# Cellphone_Incoming_Call_Detector.net
KiCad netlist of a schematic drawn in EAGLE
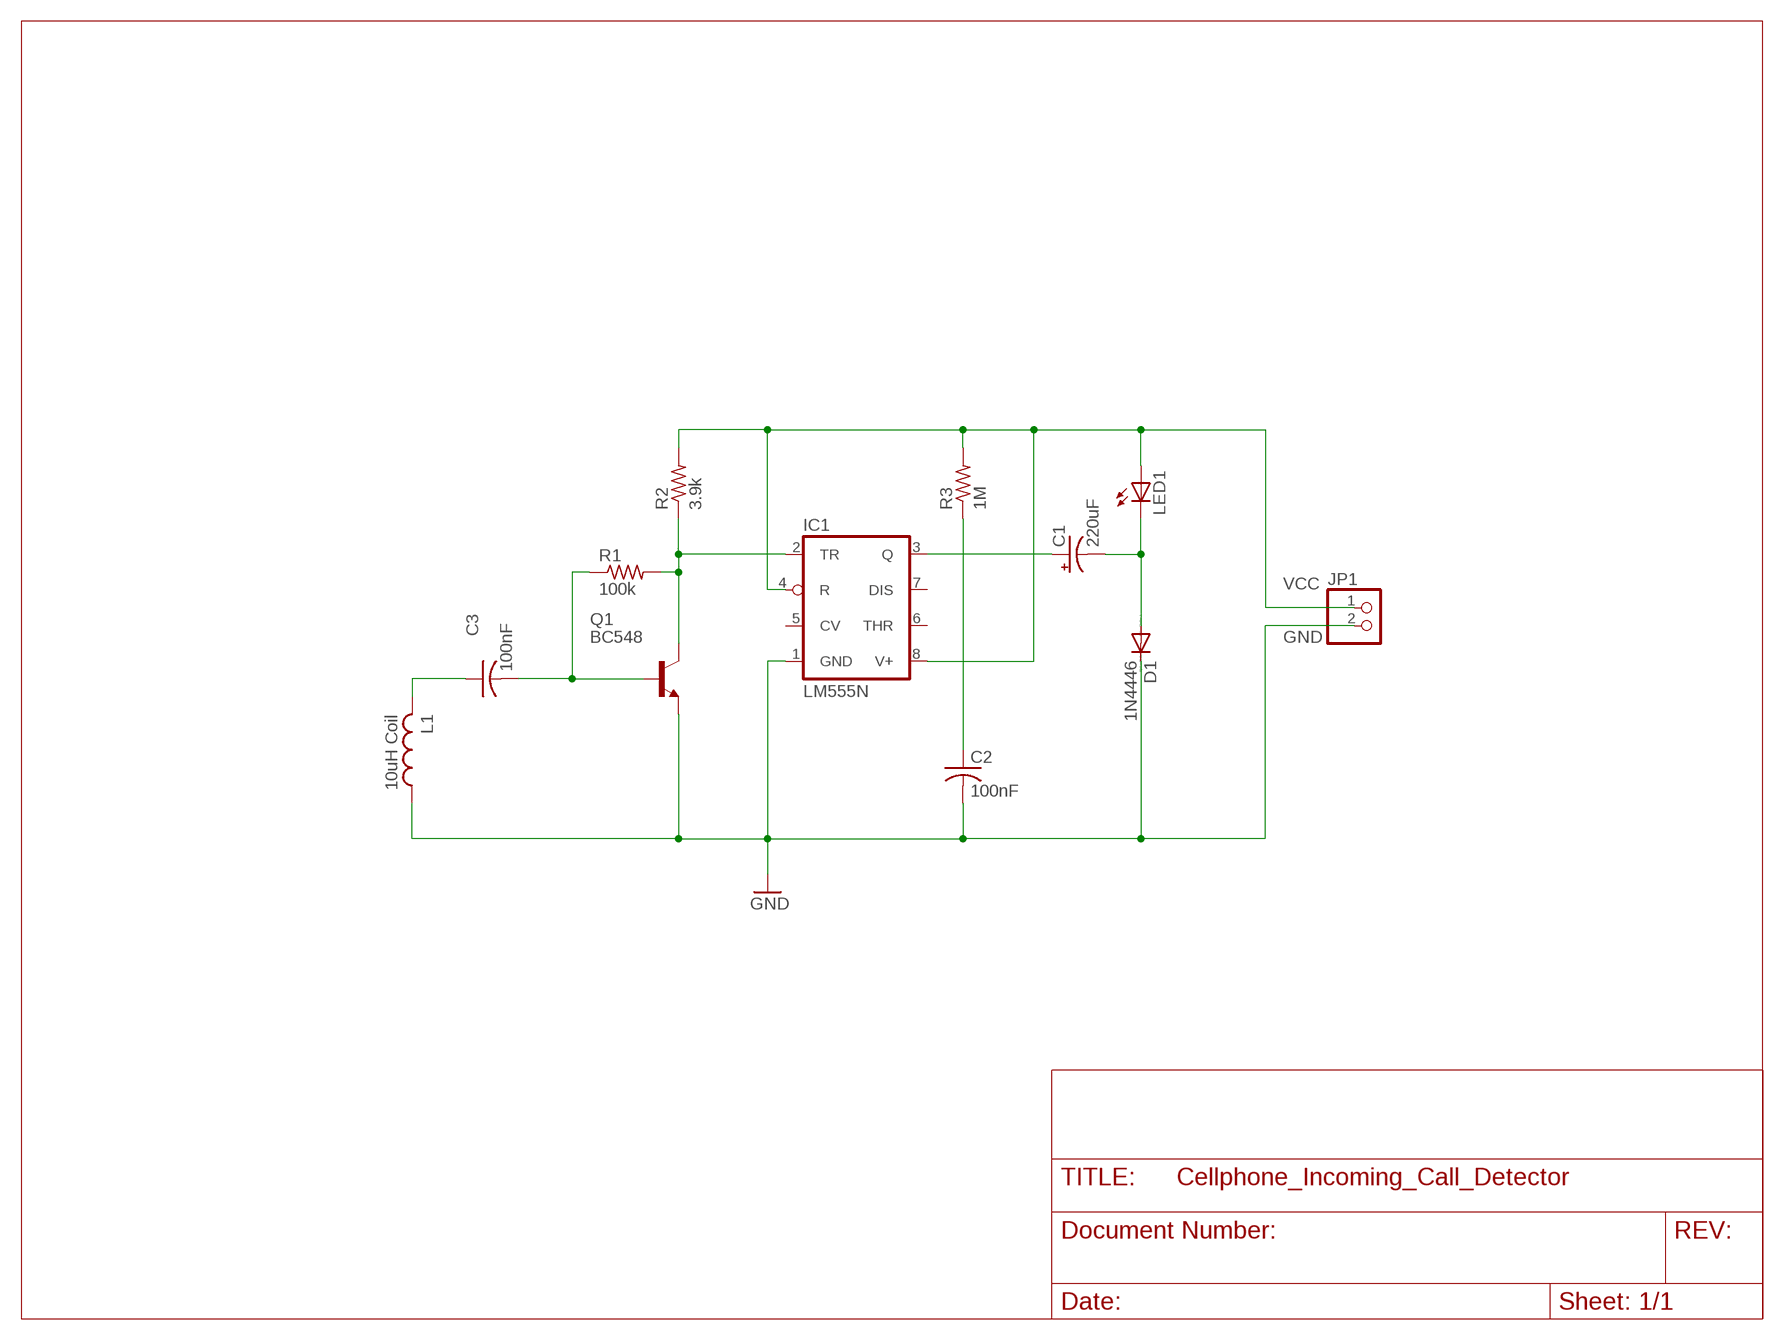
[diagram p0: schematic, sheet 1]

(export (version "E")
  (design (tool "Eeschema 10.0.6"))
  (components
    (comp (ref "C1")
      (value "220uF")
      (footprint "eagle-import:E3,5-8")
      (libsource (lib "eagle-import") (part "CPOL-USE3.5-8"))
    )
    (comp (ref "C2")
      (value "100nF")
      (footprint "eagle-import:C025-025X050")
      (libsource (lib "eagle-import") (part "C-US025-025X050"))
    )
    (comp (ref "C3")
      (value "100nF")
      (footprint "eagle-import:C025-025X050")
      (libsource (lib "eagle-import") (part "C-US025-025X050"))
    )
    (comp (ref "D1")
      (value "1N4446")
      (footprint "eagle-import:DO35-10")
      (libsource (lib "eagle-import") (part "1N4446"))
    )
    (comp (ref "IC1")
      (value "LM555N")
      (footprint "eagle-import:DIL08")
      (libsource (lib "eagle-import") (part "555NLM"))
    )
    (comp (ref "JP1")
      (value "PINHD-1X2")
      (footprint "eagle-import:1X02")
      (libsource (lib "eagle-import") (part "PINHD-1X2"))
    )
    (comp (ref "L1")
      (value "10uH Coil")
      (footprint "eagle-import:0204_7")
      (libsource (lib "eagle-import") (part "L-US0204/7"))
    )
    (comp (ref "LED1")
      (value "LED5MM")
      (footprint "eagle-import:LED5MM")
      (libsource (lib "eagle-import") (part "LED5MM"))
    )
    (comp (ref "Q1")
      (value "BC548")
      (footprint "eagle-import:TO92-EBC")
      (libsource (lib "eagle-import") (part "BC548"))
    )
    (comp (ref "R1")
      (value "100k")
      (footprint "eagle-import:0204_7")
      (libsource (lib "eagle-import") (part "R-US_0204/7"))
    )
    (comp (ref "R2")
      (value "3.9k")
      (footprint "eagle-import:0204_7")
      (libsource (lib "eagle-import") (part "R-US_0204/7"))
    )
    (comp (ref "R3")
      (value "1M")
      (footprint "eagle-import:0204_7")
      (libsource (lib "eagle-import") (part "R-US_0204/7"))
    )
  )
  (nets
    (net (code "1") (name "/VCC") (class "Default")
      (node (ref "IC1") (pin "4") (pinfunction "R_4") (pintype "input"))
      (node (ref "IC1") (pin "8") (pinfunction "V+_8") (pintype "power_in"))
      (node (ref "JP1") (pin "1") (pinfunction "1_1") (pintype "passive"))
      (node (ref "LED1") (pin "A") (pinfunction "A_A") (pintype "passive"))
      (node (ref "R2") (pin "2") (pinfunction "2_2") (pintype "passive"))
      (node (ref "R3") (pin "2") (pinfunction "2_2") (pintype "passive"))
    )
    (net (code "2") (name "GND") (class "Default")
      (node (ref "C2") (pin "2") (pinfunction "2_2") (pintype "passive"))
      (node (ref "D1") (pin "C") (pinfunction "C_C") (pintype "passive"))
      (node (ref "IC1") (pin "1") (pinfunction "GND_1") (pintype "power_in"))
      (node (ref "JP1") (pin "2") (pinfunction "2_2") (pintype "passive"))
      (node (ref "L1") (pin "1") (pinfunction "1_1") (pintype "passive"))
      (node (ref "Q1") (pin "E") (pinfunction "E_E") (pintype "passive"))
    )
    (net (code "3") (name "Net-(C2-Pad1)") (class "Default")
      (node (ref "C2") (pin "1") (pinfunction "1_1") (pintype "passive"))
      (node (ref "R3") (pin "1") (pinfunction "1_1") (pintype "passive"))
    )
    (net (code "4") (name "Net-(C3-Pad1)") (class "Default")
      (node (ref "C3") (pin "1") (pinfunction "1_1") (pintype "passive"))
      (node (ref "L1") (pin "2") (pinfunction "2_2") (pintype "passive"))
    )
    (net (code "5") (name "Net-(C3-Pad2)") (class "Default")
      (node (ref "C3") (pin "2") (pinfunction "2_2") (pintype "passive"))
      (node (ref "Q1") (pin "B") (pinfunction "B_B") (pintype "passive"))
      (node (ref "R1") (pin "1") (pinfunction "1_1") (pintype "passive"))
    )
    (net (code "6") (name "Net-(IC1-Q)") (class "Default")
      (node (ref "C1") (pin "+") (pinfunction "+_+") (pintype "passive"))
      (node (ref "IC1") (pin "3") (pinfunction "Q_3") (pintype "output"))
    )
    (net (code "7") (name "Net-(IC1-TR)") (class "Default")
      (node (ref "IC1") (pin "2") (pinfunction "TR_2") (pintype "input"))
      (node (ref "Q1") (pin "C") (pinfunction "C_C") (pintype "passive"))
      (node (ref "R1") (pin "2") (pinfunction "2_2") (pintype "passive"))
      (node (ref "R2") (pin "1") (pinfunction "1_1") (pintype "passive"))
    )
    (net (code "8") (name "Net-(LED1-C)") (class "Default")
      (node (ref "C1") (pin "-") (pinfunction "-_-") (pintype "passive"))
      (node (ref "D1") (pin "A") (pinfunction "A_A") (pintype "passive"))
      (node (ref "LED1") (pin "K") (pinfunction "C_K") (pintype "passive"))
    )
    (net (code "9") (name "unconnected-(IC1-CV-Pad5)") (class "Default")
      (node (ref "IC1") (pin "5") (pinfunction "CV_5") (pintype "input"))
    )
    (net (code "10") (name "unconnected-(IC1-DIS-Pad7)") (class "Default")
      (node (ref "IC1") (pin "7") (pinfunction "DIS_7") (pintype "input"))
    )
    (net (code "11") (name "unconnected-(IC1-THR-Pad6)") (class "Default")
      (node (ref "IC1") (pin "6") (pinfunction "THR_6") (pintype "input"))
    )
  )
)
